# Pannel.net
KiCad netlist of a schematic drawn in EasyEDA Pro
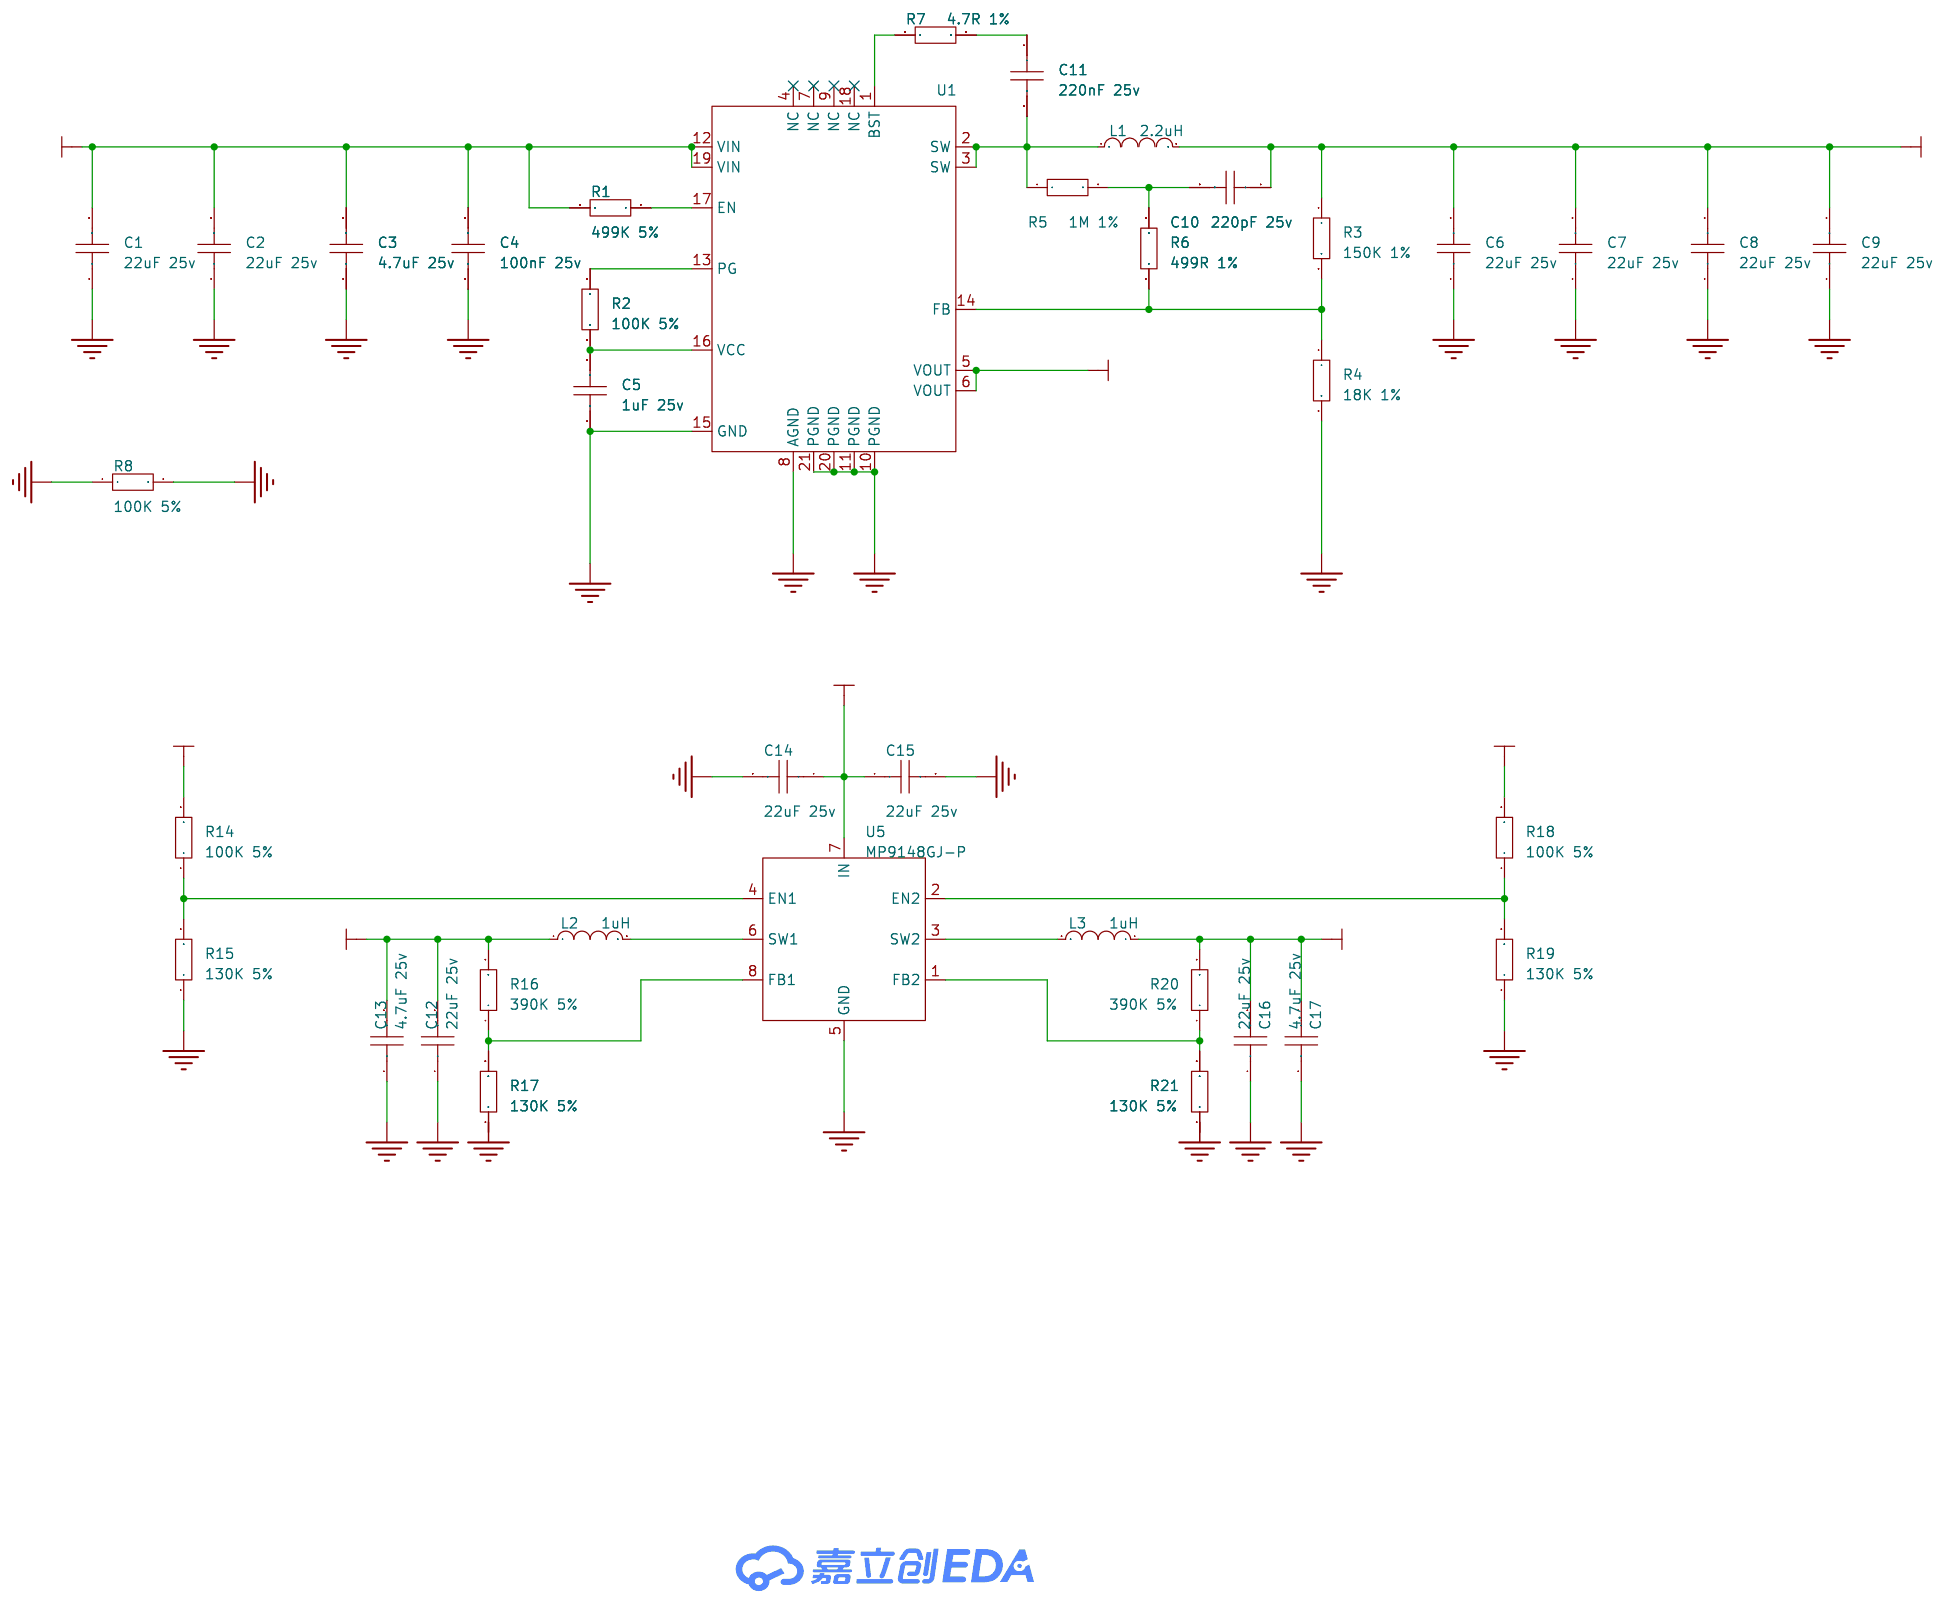
[diagram p0: PWR]
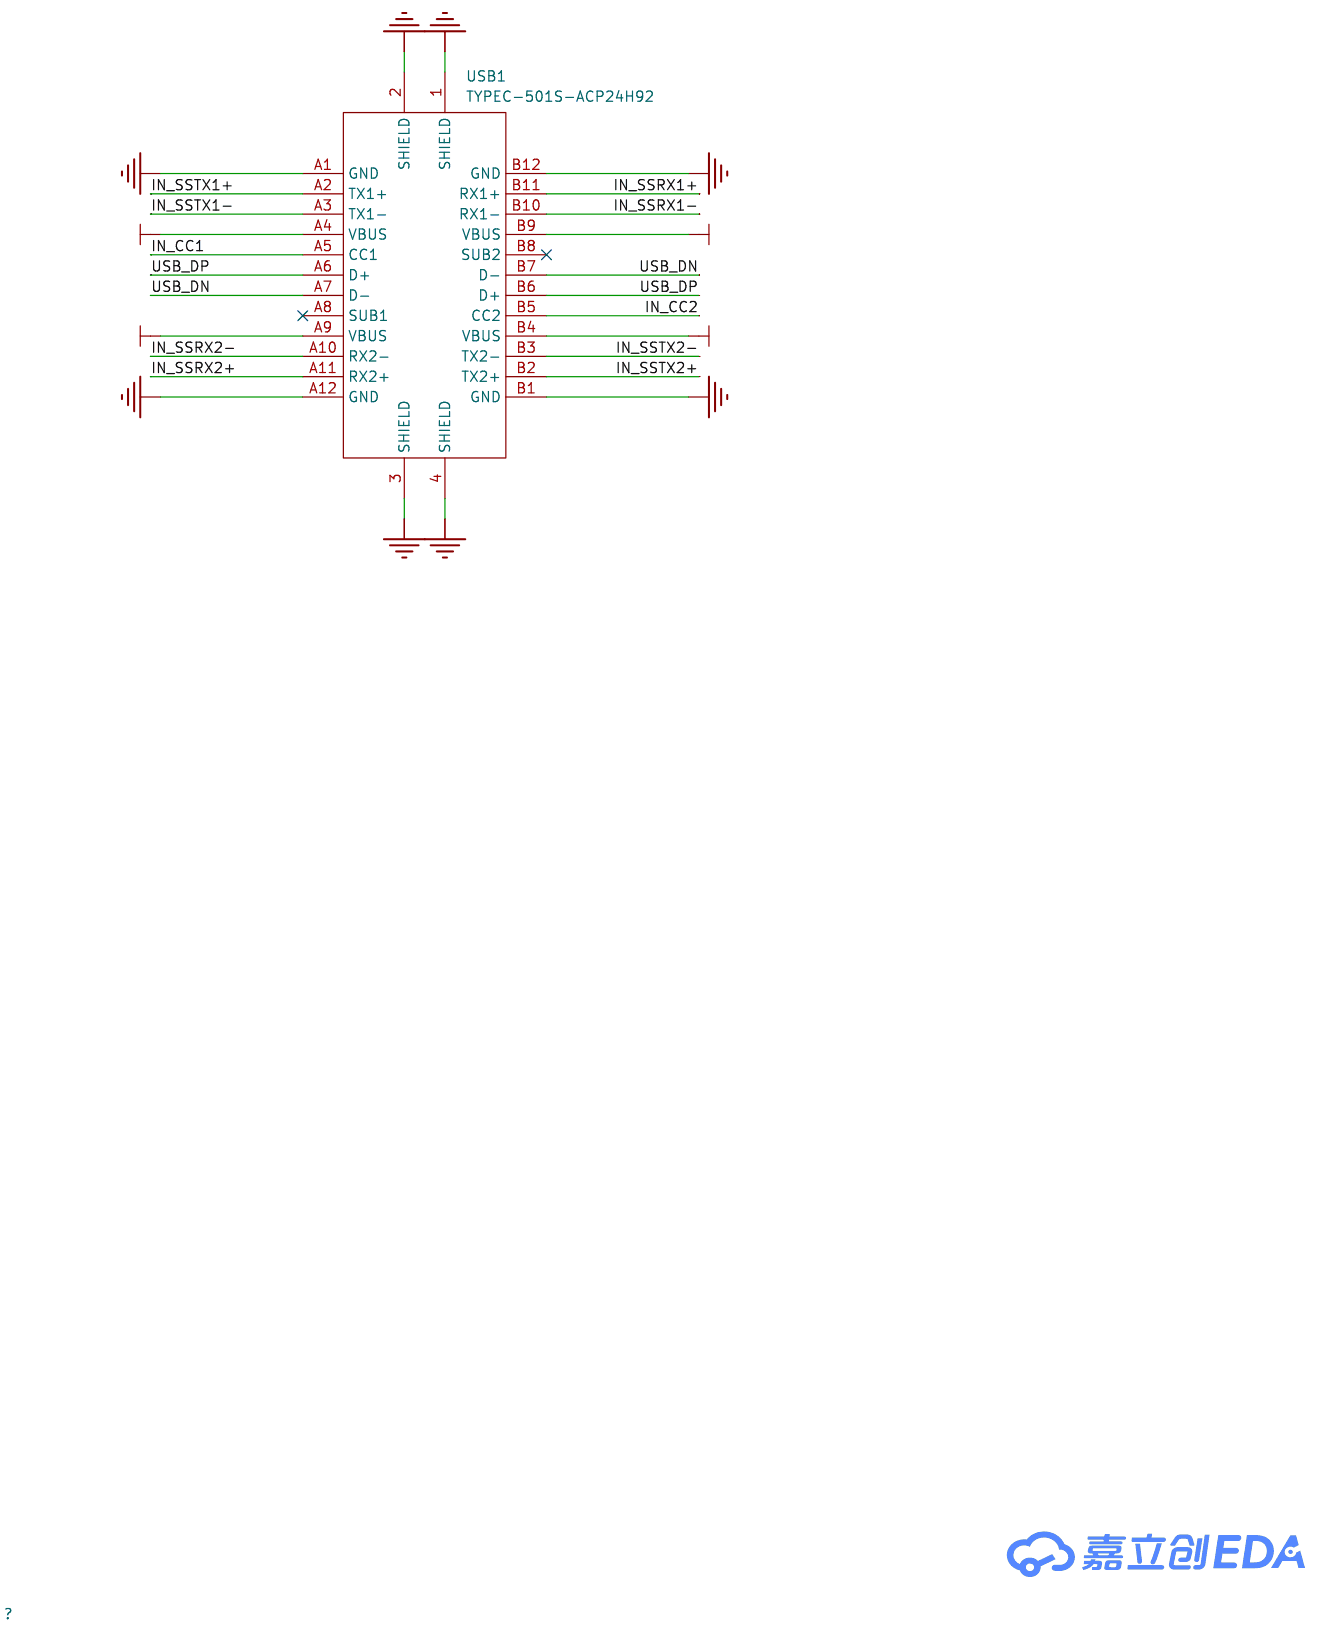
[diagram p1: Connector]
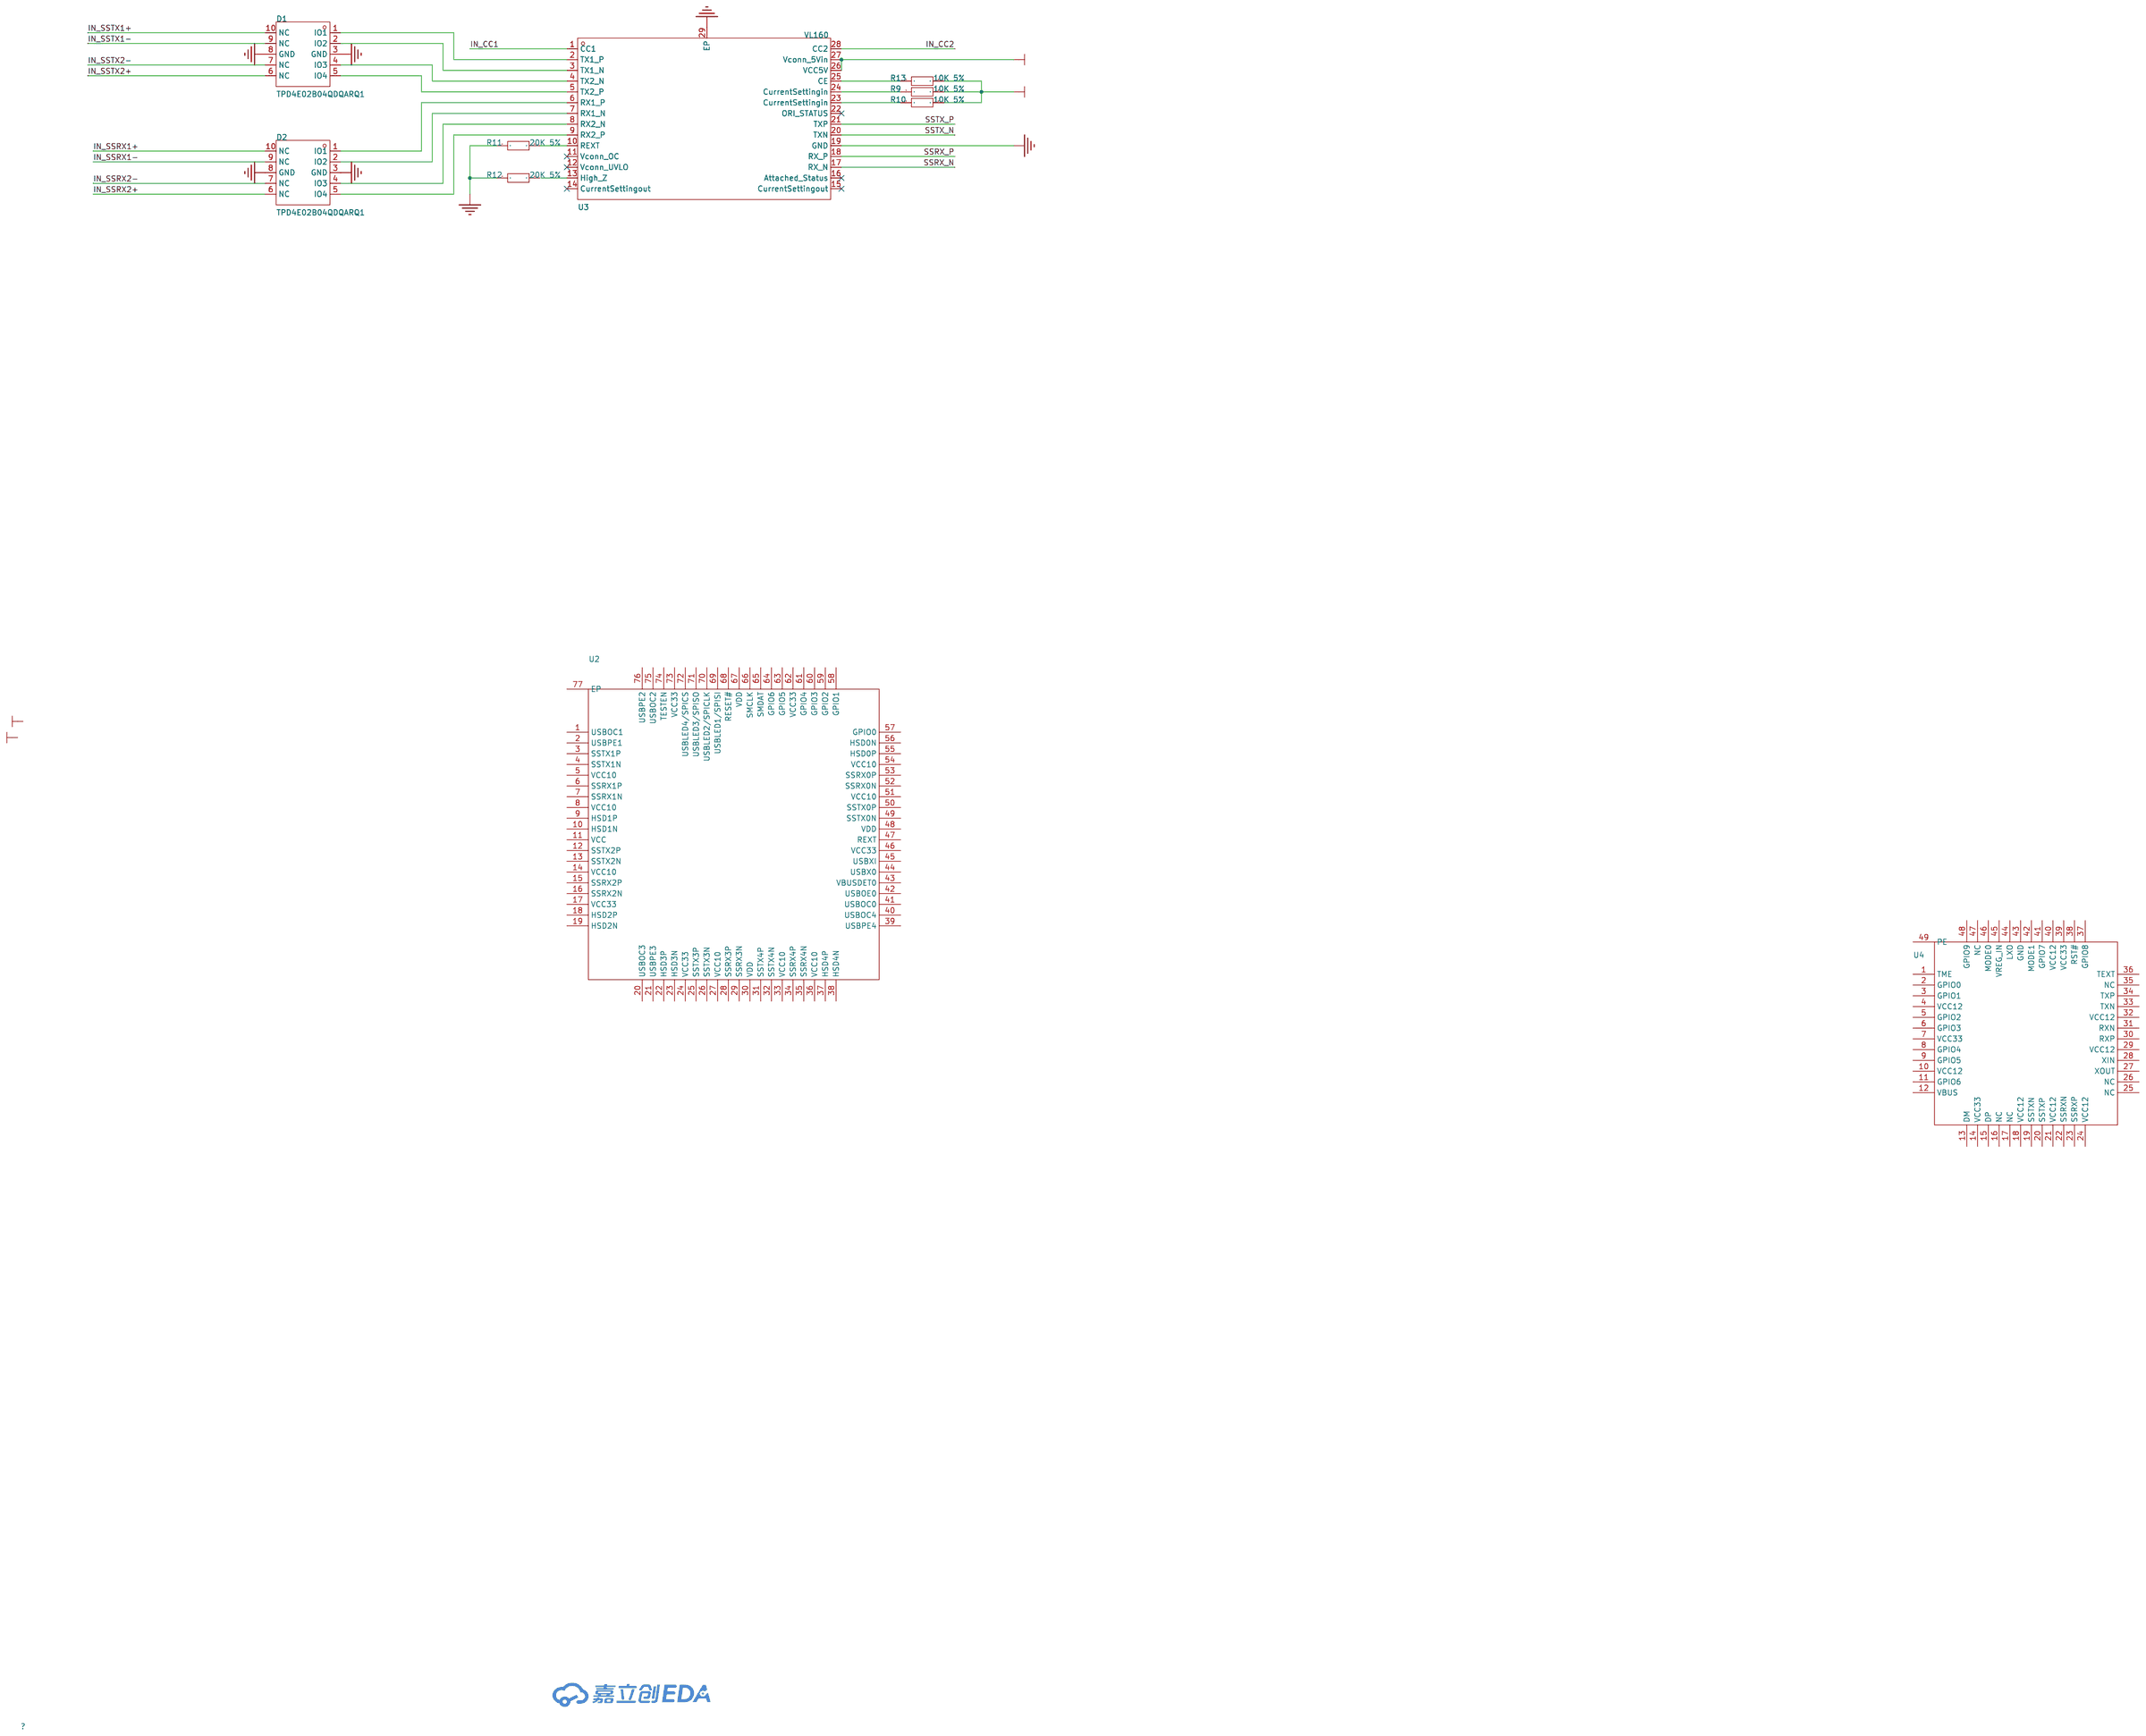
[diagram p2: Core]

(export (version "E")
  (design (tool "Eeschema 10.0.6"))
  (components
    (comp (ref "C1")
      (value "22uF 25v")
      (footprint "easyedapro:C0603")
      (libsource (lib "easyedapro") (part "Capacitance"))
    )
    (comp (ref "C2")
      (value "22uF 25v")
      (footprint "easyedapro:C0603")
      (libsource (lib "easyedapro") (part "Capacitance"))
    )
    (comp (ref "C3")
      (value "4.7uF 25v")
      (footprint "easyedapro:C0603")
      (libsource (lib "easyedapro") (part "Capacitance"))
    )
    (comp (ref "C4")
      (value "100nF 25v")
      (footprint "easyedapro:C0603")
      (libsource (lib "easyedapro") (part "Capacitance"))
    )
    (comp (ref "C5")
      (value "1uF 25v")
      (footprint "easyedapro:C0603")
      (libsource (lib "easyedapro") (part "Capacitance"))
    )
    (comp (ref "C6")
      (value "22uF 25v")
      (footprint "easyedapro:C0603")
      (libsource (lib "easyedapro") (part "Capacitance"))
    )
    (comp (ref "C7")
      (value "22uF 25v")
      (footprint "easyedapro:C0603")
      (libsource (lib "easyedapro") (part "Capacitance"))
    )
    (comp (ref "C8")
      (value "22uF 25v")
      (footprint "easyedapro:C0603")
      (libsource (lib "easyedapro") (part "Capacitance"))
    )
    (comp (ref "C9")
      (value "22uF 25v")
      (footprint "easyedapro:C0603")
      (libsource (lib "easyedapro") (part "Capacitance"))
    )
    (comp (ref "C10")
      (value "220pF 25v")
      (footprint "easyedapro:C0603")
      (libsource (lib "easyedapro") (part "Capacitance"))
    )
    (comp (ref "C11")
      (value "220nF 25v")
      (footprint "easyedapro:C0603")
      (libsource (lib "easyedapro") (part "Capacitance"))
    )
    (comp (ref "C12")
      (value "22uF 25v")
      (footprint "easyedapro:C0603")
      (libsource (lib "easyedapro") (part "Capacitance"))
    )
    (comp (ref "C13")
      (value "4.7uF 25v")
      (footprint "easyedapro:C0603")
      (libsource (lib "easyedapro") (part "Capacitance"))
    )
    (comp (ref "C14")
      (value "22uF 25v")
      (footprint "easyedapro:C0603")
      (libsource (lib "easyedapro") (part "Capacitance"))
    )
    (comp (ref "C15")
      (value "22uF 25v")
      (footprint "easyedapro:C0603")
      (libsource (lib "easyedapro") (part "Capacitance"))
    )
    (comp (ref "C16")
      (value "22uF 25v")
      (footprint "easyedapro:C0603")
      (libsource (lib "easyedapro") (part "Capacitance"))
    )
    (comp (ref "C17")
      (value "4.7uF 25v")
      (footprint "easyedapro:C0603")
      (libsource (lib "easyedapro") (part "Capacitance"))
    )
    (comp (ref "L1")
      (value "2.2uH")
      (footprint "easyedapro:L0603")
      (libsource (lib "easyedapro") (part "SDFL1608S100KTF"))
    )
    (comp (ref "L2")
      (value "1uH")
      (footprint "easyedapro:IND-SMD_L4.5-W4.1_YXMAA0402")
      (description "电感值:3.3uH;精度:±20%;额定电流:-;饱和电流(Isat):3.1A;直流电阻(DCR):65mΩ;")
      (fields (field (name "Manufacturer Part") "MDA4020-3R3M") (field (name "Manufacturer") "KOHERelec(科或)"))
      (libsource (lib "easyedapro") (part "MDA4020-3R3M"))
    )
    (comp (ref "L3")
      (value "1uH")
      (footprint "easyedapro:IND-SMD_L4.5-W4.1_YXMAA0402")
      (description "电感值:3.3uH;精度:±20%;额定电流:-;饱和电流(Isat):3.1A;直流电阻(DCR):65mΩ;")
      (fields (field (name "Manufacturer Part") "MDA4020-3R3M") (field (name "Manufacturer") "KOHERelec(科或)"))
      (libsource (lib "easyedapro") (part "MDA4020-3R3M"))
    )
    (comp (ref "R1")
      (value "499K 5%")
      (footprint "easyedapro:R0603")
      (libsource (lib "easyedapro") (part "电阻"))
    )
    (comp (ref "R2")
      (value "100K 5%")
      (footprint "easyedapro:R0603")
      (libsource (lib "easyedapro") (part "电阻"))
    )
    (comp (ref "R3")
      (value "150K 1%")
      (footprint "easyedapro:R0603")
      (libsource (lib "easyedapro") (part "电阻"))
    )
    (comp (ref "R4")
      (value "18K 1%")
      (footprint "easyedapro:R0603")
      (libsource (lib "easyedapro") (part "电阻"))
    )
    (comp (ref "R5")
      (value "1M 1%")
      (footprint "easyedapro:R0603")
      (libsource (lib "easyedapro") (part "电阻"))
    )
    (comp (ref "R6")
      (value "499R 1%")
      (footprint "easyedapro:R0603")
      (libsource (lib "easyedapro") (part "电阻"))
    )
    (comp (ref "R7")
      (value "4.7R 1%")
      (footprint "easyedapro:R0603")
      (libsource (lib "easyedapro") (part "电阻"))
    )
    (comp (ref "R8")
      (value "100K 5%")
      (footprint "easyedapro:R0603")
      (libsource (lib "easyedapro") (part "电阻"))
    )
    (comp (ref "R14")
      (value "100K 5%")
      (footprint "easyedapro:R0603")
      (libsource (lib "easyedapro") (part "电阻"))
    )
    (comp (ref "R15")
      (value "130K 5%")
      (footprint "easyedapro:R0603")
      (libsource (lib "easyedapro") (part "电阻"))
    )
    (comp (ref "R16")
      (value "390K 5%")
      (footprint "easyedapro:R0603")
      (libsource (lib "easyedapro") (part "电阻"))
    )
    (comp (ref "R17")
      (value "130K 5%")
      (footprint "easyedapro:R0603")
      (libsource (lib "easyedapro") (part "电阻"))
    )
    (comp (ref "R18")
      (value "100K 5%")
      (footprint "easyedapro:R0603")
      (libsource (lib "easyedapro") (part "电阻"))
    )
    (comp (ref "R19")
      (value "130K 5%")
      (footprint "easyedapro:R0603")
      (libsource (lib "easyedapro") (part "电阻"))
    )
    (comp (ref "R20")
      (value "390K 5%")
      (footprint "easyedapro:R0603")
      (libsource (lib "easyedapro") (part "电阻"))
    )
    (comp (ref "R21")
      (value "130K 5%")
      (footprint "easyedapro:R0603")
      (libsource (lib "easyedapro") (part "电阻"))
    )
    (comp (ref "U1") (value "~") (libsource (lib "easyedapro") (part "MP8757")))
    (comp (ref "U5")
      (value "MP9148GJ-P")
      (footprint "easyedapro:TSOT-23-8_L2.9-W1.6-P0.65-LS2.8-BR")
      (description "功能类型:降压型;输出类型:可调;工作电压:2.7V~6V;输出电压:608mV~5.5V;输出电流:1A;")
      (libsource (lib "easyedapro") (part "MP9148GJ-P"))
    )
    (comp (ref "USB1")
      (value "TYPEC-501S-ACP24H92")
      (footprint "easyedapro:USB-C-SMD_TYPEC-501S-ACP24H92")
      (fields (field (name "Manufacturer") "XUNPU(讯普)"))
      (libsource (lib "easyedapro") (part "TYPEC-501S-ACP24H92"))
    )
    (comp (ref "D1")
      (value "TPD4E02B04QDQARQ1")
      (footprint "easyedapro:USON-10_L2.5-W1.0-P0.50-BL")
      (fields (field (name "Manufacturer") "TI(德州仪器)"))
      (libsource (lib "easyedapro") (part "TPD4E02B04QDQARQ1"))
    )
    (comp (ref "D2")
      (value "TPD4E02B04QDQARQ1")
      (footprint "easyedapro:USON-10_L2.5-W1.0-P0.50-BL")
      (fields (field (name "Manufacturer") "TI(德州仪器)"))
      (libsource (lib "easyedapro") (part "TPD4E02B04QDQARQ1"))
    )
    (comp (ref "R9")
      (value "10K 5%")
      (footprint "easyedapro:R0603")
      (libsource (lib "easyedapro") (part "电阻"))
    )
    (comp (ref "R10")
      (value "10K 5%")
      (footprint "easyedapro:R0603")
      (libsource (lib "easyedapro") (part "电阻"))
    )
    (comp (ref "R11")
      (value "20K 5%")
      (footprint "easyedapro:R0603")
      (libsource (lib "easyedapro") (part "电阻"))
    )
    (comp (ref "R12")
      (value "20K 5%")
      (footprint "easyedapro:R0603")
      (libsource (lib "easyedapro") (part "电阻"))
    )
    (comp (ref "R13")
      (value "10K 5%")
      (footprint "easyedapro:R0603")
      (libsource (lib "easyedapro") (part "电阻"))
    )
    (comp (ref "U2")
      (value "~")
      (footprint "easyedapro:QFN-76_L9.0-W9.0-P0.40-TL-EP")
      (libsource (lib "easyedapro") (part "VL822"))
    )
    (comp (ref "U3")
      (value "VL160")
      (footprint "easyedapro:MQFN-28_L4.5-W3.5-P0.40-BL-EP")
      (description "应用功能:-;接口协议:-;")
      (libsource (lib "easyedapro") (part "VL160"))
    )
    (comp (ref "U4")
      (value "~")
      (footprint "easyedapro:QFN-48_L5.0-W5.0-P0.35-BL-EP3.7-1")
      (libsource (lib "easyedapro") (part "JMS578"))
    )
  )
  (nets
    (net (code "1") (name "GND") (class "Default")
      (node (ref "C1") (pin "1") (pinfunction "1_1") (pintype "input"))
      (node (ref "C12") (pin "1") (pinfunction "1_1") (pintype "input"))
      (node (ref "C13") (pin "1") (pinfunction "1_1") (pintype "input"))
      (node (ref "C14") (pin "2") (pinfunction "2_2") (pintype "input"))
      (node (ref "C15") (pin "2") (pinfunction "2_2") (pintype "input"))
      (node (ref "C16") (pin "1") (pinfunction "1_1") (pintype "input"))
      (node (ref "C17") (pin "1") (pinfunction "1_1") (pintype "input"))
      (node (ref "C2") (pin "1") (pinfunction "1_1") (pintype "input"))
      (node (ref "C3") (pin "1") (pinfunction "1_1") (pintype "input"))
      (node (ref "C4") (pin "1") (pinfunction "1_1") (pintype "input"))
      (node (ref "C5") (pin "1") (pinfunction "1_1") (pintype "input"))
      (node (ref "C6") (pin "1") (pinfunction "1_1") (pintype "input"))
      (node (ref "C7") (pin "1") (pinfunction "1_1") (pintype "input"))
      (node (ref "C8") (pin "1") (pinfunction "1_1") (pintype "input"))
      (node (ref "C9") (pin "1") (pinfunction "1_1") (pintype "input"))
      (node (ref "D1") (pin "3") (pinfunction "GND_3") (pintype "unspecified"))
      (node (ref "D1") (pin "8") (pinfunction "GND_8") (pintype "unspecified"))
      (node (ref "D2") (pin "3") (pinfunction "GND_3") (pintype "unspecified"))
      (node (ref "D2") (pin "8") (pinfunction "GND_8") (pintype "unspecified"))
      (node (ref "R11") (pin "1") (pinfunction "1_1") (pintype "input"))
      (node (ref "R12") (pin "1") (pinfunction "1_1") (pintype "input"))
      (node (ref "R15") (pin "1") (pinfunction "1_1") (pintype "input"))
      (node (ref "R17") (pin "1") (pinfunction "1_1") (pintype "input"))
      (node (ref "R19") (pin "1") (pinfunction "1_1") (pintype "input"))
      (node (ref "R21") (pin "1") (pinfunction "1_1") (pintype "input"))
      (node (ref "R4") (pin "2") (pinfunction "2_2") (pintype "input"))
      (node (ref "R8") (pin "1") (pinfunction "1_1") (pintype "input"))
      (node (ref "U1") (pin "15") (pinfunction "GND_15") (pintype "unspecified"))
      (node (ref "U1") (pin "8") (pinfunction "AGND_8") (pintype "unspecified"))
      (node (ref "U3") (pin "19") (pinfunction "GND_19") (pintype "unspecified"))
      (node (ref "U3") (pin "29") (pinfunction "EP_29") (pintype "unspecified"))
      (node (ref "U5") (pin "5") (pinfunction "GND_5") (pintype "unspecified"))
      (node (ref "USB1") (pin "1") (pinfunction "SHIELD_1") (pintype "unspecified"))
      (node (ref "USB1") (pin "2") (pinfunction "SHIELD_2") (pintype "unspecified"))
      (node (ref "USB1") (pin "3") (pinfunction "SHIELD_3") (pintype "unspecified"))
      (node (ref "USB1") (pin "4") (pinfunction "SHIELD_4") (pintype "unspecified"))
      (node (ref "USB1") (pin "A1") (pinfunction "GND_A1") (pintype "unspecified"))
      (node (ref "USB1") (pin "A12") (pinfunction "GND_A12") (pintype "unspecified"))
      (node (ref "USB1") (pin "B1") (pinfunction "GND_B1") (pintype "unspecified"))
      (node (ref "USB1") (pin "B12") (pinfunction "GND_B12") (pintype "unspecified"))
    )
    (net (code "2") (name "IN_CC1") (class "Default")
      (node (ref "U3") (pin "1") (pinfunction "CC1_1") (pintype "unspecified"))
      (node (ref "USB1") (pin "A5") (pinfunction "CC1_A5") (pintype "unspecified"))
    )
    (net (code "3") (name "IN_CC2") (class "Default")
      (node (ref "U3") (pin "28") (pinfunction "CC2_28") (pintype "unspecified"))
      (node (ref "USB1") (pin "B5") (pinfunction "CC2_B5") (pintype "unspecified"))
    )
    (net (code "4") (name "IN_SSRX1+") (class "Default")
      (node (ref "D2") (pin "10") (pinfunction "NC_10") (pintype "unspecified"))
      (node (ref "USB1") (pin "B11") (pinfunction "RX1+_B11") (pintype "unspecified"))
    )
    (net (code "5") (name "IN_SSRX1-") (class "Default")
      (node (ref "D2") (pin "9") (pinfunction "NC_9") (pintype "unspecified"))
      (node (ref "USB1") (pin "B10") (pinfunction "RX1-_B10") (pintype "unspecified"))
    )
    (net (code "6") (name "IN_SSRX2+") (class "Default")
      (node (ref "D2") (pin "6") (pinfunction "NC_6") (pintype "unspecified"))
      (node (ref "USB1") (pin "A11") (pinfunction "RX2+_A11") (pintype "unspecified"))
    )
    (net (code "7") (name "IN_SSRX2-") (class "Default")
      (node (ref "D2") (pin "7") (pinfunction "NC_7") (pintype "unspecified"))
      (node (ref "USB1") (pin "A10") (pinfunction "RX2-_A10") (pintype "unspecified"))
    )
    (net (code "8") (name "IN_SSTX1+") (class "Default")
      (node (ref "D1") (pin "10") (pinfunction "NC_10") (pintype "unspecified"))
      (node (ref "USB1") (pin "A2") (pinfunction "TX1+_A2") (pintype "unspecified"))
    )
    (net (code "9") (name "IN_SSTX1-") (class "Default")
      (node (ref "D1") (pin "9") (pinfunction "NC_9") (pintype "unspecified"))
      (node (ref "USB1") (pin "A3") (pinfunction "TX1-_A3") (pintype "unspecified"))
    )
    (net (code "10") (name "IN_SSTX2+") (class "Default")
      (node (ref "D1") (pin "6") (pinfunction "NC_6") (pintype "unspecified"))
      (node (ref "USB1") (pin "B2") (pinfunction "TX2+_B2") (pintype "unspecified"))
    )
    (net (code "11") (name "IN_SSTX2-") (class "Default")
      (node (ref "D1") (pin "7") (pinfunction "NC_7") (pintype "unspecified"))
      (node (ref "USB1") (pin "B3") (pinfunction "TX2-_B3") (pintype "unspecified"))
    )
    (net (code "12") (name "Net-(C10-Pad2)") (class "Default")
      (node (ref "C10") (pin "2") (pinfunction "2_2") (pintype "input"))
      (node (ref "R5") (pin "2") (pinfunction "2_2") (pintype "input"))
      (node (ref "R6") (pin "2") (pinfunction "2_2") (pintype "input"))
    )
    (net (code "13") (name "Net-(C11-Pad1)") (class "Default")
      (node (ref "C11") (pin "1") (pinfunction "1_1") (pintype "input"))
      (node (ref "R7") (pin "2") (pinfunction "2_2") (pintype "input"))
    )
    (net (code "14") (name "Net-(C11-Pad2)") (class "Default")
      (node (ref "C11") (pin "2") (pinfunction "2_2") (pintype "input"))
      (node (ref "L1") (pin "1") (pinfunction "1_1") (pintype "unspecified"))
      (node (ref "R5") (pin "1") (pinfunction "1_1") (pintype "input"))
      (node (ref "U1") (pin "2") (pinfunction "SW_2") (pintype "unspecified"))
      (node (ref "U1") (pin "3") (pinfunction "SW_3") (pintype "unspecified"))
    )
    (net (code "15") (name "Net-(D1-IO1)") (class "Default")
      (node (ref "D1") (pin "1") (pinfunction "IO1_1") (pintype "unspecified"))
      (node (ref "U3") (pin "2") (pinfunction "TX1_P_2") (pintype "unspecified"))
    )
    (net (code "16") (name "Net-(D1-IO2)") (class "Default")
      (node (ref "D1") (pin "2") (pinfunction "IO2_2") (pintype "unspecified"))
      (node (ref "U3") (pin "3") (pinfunction "TX1_N_3") (pintype "unspecified"))
    )
    (net (code "17") (name "Net-(D1-IO3)") (class "Default")
      (node (ref "D1") (pin "4") (pinfunction "IO3_4") (pintype "unspecified"))
      (node (ref "U3") (pin "4") (pinfunction "TX2_N_4") (pintype "unspecified"))
    )
    (net (code "18") (name "Net-(D1-IO4)") (class "Default")
      (node (ref "D1") (pin "5") (pinfunction "IO4_5") (pintype "unspecified"))
      (node (ref "U3") (pin "5") (pinfunction "TX2_P_5") (pintype "unspecified"))
    )
    (net (code "19") (name "Net-(D2-IO1)") (class "Default")
      (node (ref "D2") (pin "1") (pinfunction "IO1_1") (pintype "unspecified"))
      (node (ref "U3") (pin "6") (pinfunction "RX1_P_6") (pintype "unspecified"))
    )
    (net (code "20") (name "Net-(D2-IO2)") (class "Default")
      (node (ref "D2") (pin "2") (pinfunction "IO2_2") (pintype "unspecified"))
      (node (ref "U3") (pin "7") (pinfunction "RX1_N_7") (pintype "unspecified"))
    )
    (net (code "21") (name "Net-(D2-IO3)") (class "Default")
      (node (ref "D2") (pin "4") (pinfunction "IO3_4") (pintype "unspecified"))
      (node (ref "U3") (pin "8") (pinfunction "RX2_N_8") (pintype "unspecified"))
    )
    (net (code "22") (name "Net-(D2-IO4)") (class "Default")
      (node (ref "D2") (pin "5") (pinfunction "IO4_5") (pintype "unspecified"))
      (node (ref "U3") (pin "9") (pinfunction "RX2_P_9") (pintype "unspecified"))
    )
    (net (code "23") (name "Net-(R9-Pad1)") (class "Default")
      (node (ref "R9") (pin "1") (pinfunction "1_1") (pintype "input"))
      (node (ref "U3") (pin "24") (pinfunction "CurrentSettingin_24") (pintype "unspecified"))
    )
    (net (code "24") (name "Net-(R10-Pad1)") (class "Default")
      (node (ref "R10") (pin "1") (pinfunction "1_1") (pintype "input"))
      (node (ref "U3") (pin "23") (pinfunction "CurrentSettingin_23") (pintype "unspecified"))
    )
    (net (code "25") (name "Net-(U1-BST)") (class "Default")
      (node (ref "R7") (pin "1") (pinfunction "1_1") (pintype "input"))
      (node (ref "U1") (pin "1") (pinfunction "BST_1") (pintype "unspecified"))
    )
    (net (code "26") (name "Net-(U1-EN)") (class "Default")
      (node (ref "R1") (pin "1") (pinfunction "1_1") (pintype "input"))
      (node (ref "U1") (pin "17") (pinfunction "EN_17") (pintype "unspecified"))
    )
    (net (code "27") (name "Net-(U1-FB)") (class "Default")
      (node (ref "R3") (pin "2") (pinfunction "2_2") (pintype "input"))
      (node (ref "R4") (pin "1") (pinfunction "1_1") (pintype "input"))
      (node (ref "R6") (pin "1") (pinfunction "1_1") (pintype "input"))
      (node (ref "U1") (pin "14") (pinfunction "FB_14") (pintype "unspecified"))
    )
    (net (code "28") (name "Net-(U1-PG)") (class "Default")
      (node (ref "R2") (pin "1") (pinfunction "1_1") (pintype "input"))
      (node (ref "U1") (pin "13") (pinfunction "PG_13") (pintype "unspecified"))
    )
    (net (code "29") (name "Net-(U1-VCC)") (class "Default")
      (node (ref "C5") (pin "2") (pinfunction "2_2") (pintype "input"))
      (node (ref "R2") (pin "2") (pinfunction "2_2") (pintype "input"))
      (node (ref "U1") (pin "16") (pinfunction "VCC_16") (pintype "unspecified"))
    )
    (net (code "30") (name "Net-(U3-CE)") (class "Default")
      (node (ref "R13") (pin "1") (pinfunction "1_1") (pintype "input"))
      (node (ref "U3") (pin "25") (pinfunction "CE_25") (pintype "unspecified"))
    )
    (net (code "31") (name "Net-(U3-REXT)") (class "Default")
      (node (ref "R11") (pin "2") (pinfunction "2_2") (pintype "input"))
      (node (ref "U3") (pin "10") (pinfunction "REXT_10") (pintype "unspecified"))
    )
    (net (code "32") (name "Net-(U5-EN1)") (class "Default")
      (node (ref "R14") (pin "1") (pinfunction "1_1") (pintype "input"))
      (node (ref "R15") (pin "2") (pinfunction "2_2") (pintype "input"))
      (node (ref "U5") (pin "4") (pinfunction "EN1_4") (pintype "unspecified"))
    )
    (net (code "33") (name "Net-(U5-EN2)") (class "Default")
      (node (ref "R18") (pin "1") (pinfunction "1_1") (pintype "input"))
      (node (ref "R19") (pin "2") (pinfunction "2_2") (pintype "input"))
      (node (ref "U5") (pin "2") (pinfunction "EN2_2") (pintype "unspecified"))
    )
    (net (code "34") (name "Net-(U5-FB1)") (class "Default")
      (node (ref "R16") (pin "1") (pinfunction "1_1") (pintype "input"))
      (node (ref "R17") (pin "2") (pinfunction "2_2") (pintype "input"))
      (node (ref "U5") (pin "8") (pinfunction "FB1_8") (pintype "unspecified"))
    )
    (net (code "35") (name "Net-(U5-FB2)") (class "Default")
      (node (ref "R20") (pin "1") (pinfunction "1_1") (pintype "input"))
      (node (ref "R21") (pin "2") (pinfunction "2_2") (pintype "input"))
      (node (ref "U5") (pin "1") (pinfunction "FB2_1") (pintype "unspecified"))
    )
    (net (code "36") (name "Net-(U5-SW1)") (class "Default")
      (node (ref "L2") (pin "2") (pinfunction "2_2") (pintype "unspecified"))
      (node (ref "U5") (pin "6") (pinfunction "SW1_6") (pintype "unspecified"))
    )
    (net (code "37") (name "Net-(U5-SW2)") (class "Default")
      (node (ref "L3") (pin "2") (pinfunction "2_2") (pintype "unspecified"))
      (node (ref "U5") (pin "3") (pinfunction "SW2_3") (pintype "unspecified"))
    )
    (net (code "38") (name "PGND") (class "Default")
      (node (ref "R8") (pin "2") (pinfunction "2_2") (pintype "input"))
      (node (ref "U1") (pin "10") (pinfunction "PGND_10") (pintype "unspecified"))
      (node (ref "U1") (pin "11") (pinfunction "PGND_11") (pintype "unspecified"))
      (node (ref "U1") (pin "20") (pinfunction "PGND_20") (pintype "unspecified"))
      (node (ref "U1") (pin "21") (pinfunction "PGND_21") (pintype "unspecified"))
    )
    (net (code "39") (name "SSRX_N") (class "Default")
      (node (ref "U3") (pin "17") (pinfunction "RX_N_17") (pintype "unspecified"))
    )
    (net (code "40") (name "SSRX_P") (class "Default")
      (node (ref "U3") (pin "18") (pinfunction "RX_P_18") (pintype "unspecified"))
    )
    (net (code "41") (name "SSTX_N") (class "Default")
      (node (ref "U3") (pin "20") (pinfunction "TXN_20") (pintype "unspecified"))
    )
    (net (code "42") (name "SSTX_P") (class "Default")
      (node (ref "U3") (pin "21") (pinfunction "TXP_21") (pintype "unspecified"))
    )
    (net (code "43") (name "USB_DN") (class "Default")
      (node (ref "USB1") (pin "A7") (pinfunction "D-_A7") (pintype "unspecified"))
      (node (ref "USB1") (pin "B7") (pinfunction "D-_B7") (pintype "unspecified"))
    )
    (net (code "44") (name "USB_DP") (class "Default")
      (node (ref "USB1") (pin "A6") (pinfunction "D+_A6") (pintype "unspecified"))
      (node (ref "USB1") (pin "B6") (pinfunction "D+_B6") (pintype "unspecified"))
    )
    (net (code "45") (name "VBUS") (class "Default")
      (node (ref "C14") (pin "1") (pinfunction "1_1") (pintype "input"))
      (node (ref "C15") (pin "1") (pinfunction "1_1") (pintype "input"))
      (node (ref "R10") (pin "2") (pinfunction "2_2") (pintype "input"))
      (node (ref "R13") (pin "2") (pinfunction "2_2") (pintype "input"))
      (node (ref "R14") (pin "2") (pinfunction "2_2") (pintype "input"))
      (node (ref "R18") (pin "2") (pinfunction "2_2") (pintype "input"))
      (node (ref "R9") (pin "2") (pinfunction "2_2") (pintype "input"))
      (node (ref "U3") (pin "26") (pinfunction "VCC5V_26") (pintype "unspecified"))
      (node (ref "U3") (pin "27") (pinfunction "Vconn_5Vin_27") (pintype "unspecified"))
      (node (ref "U5") (pin "7") (pinfunction "IN_7") (pintype "unspecified"))
      (node (ref "USB1") (pin "A4") (pinfunction "VBUS_A4") (pintype "unspecified"))
      (node (ref "USB1") (pin "A9") (pinfunction "VBUS_A9") (pintype "unspecified"))
      (node (ref "USB1") (pin "B4") (pinfunction "VBUS_B4") (pintype "unspecified"))
      (node (ref "USB1") (pin "B9") (pinfunction "VBUS_B9") (pintype "unspecified"))
    )
    (net (code "46") (name "VCC1V0") (class "Default")
      (node (ref "C12") (pin "2") (pinfunction "2_2") (pintype "input"))
      (node (ref "C13") (pin "2") (pinfunction "2_2") (pintype "input"))
      (node (ref "L2") (pin "1") (pinfunction "1_1") (pintype "unspecified"))
      (node (ref "R16") (pin "2") (pinfunction "2_2") (pintype "input"))
    )
    (net (code "47") (name "VCC3V3") (class "Default")
      (node (ref "C16") (pin "2") (pinfunction "2_2") (pintype "input"))
      (node (ref "C17") (pin "2") (pinfunction "2_2") (pintype "input"))
      (node (ref "L3") (pin "1") (pinfunction "1_1") (pintype "unspecified"))
      (node (ref "R20") (pin "2") (pinfunction "2_2") (pintype "input"))
    )
    (net (code "48") (name "VCC5V") (class "Default")
      (node (ref "C10") (pin "1") (pinfunction "1_1") (pintype "input"))
      (node (ref "C6") (pin "2") (pinfunction "2_2") (pintype "input"))
      (node (ref "C7") (pin "2") (pinfunction "2_2") (pintype "input"))
      (node (ref "C8") (pin "2") (pinfunction "2_2") (pintype "input"))
      (node (ref "C9") (pin "2") (pinfunction "2_2") (pintype "input"))
      (node (ref "L1") (pin "2") (pinfunction "2_2") (pintype "unspecified"))
      (node (ref "R3") (pin "1") (pinfunction "1_1") (pintype "input"))
      (node (ref "U1") (pin "5") (pinfunction "VOUT_5") (pintype "unspecified"))
      (node (ref "U1") (pin "6") (pinfunction "VOUT_6") (pintype "unspecified"))
    )
    (net (code "49") (name "VCC12V") (class "Default")
      (node (ref "C1") (pin "2") (pinfunction "2_2") (pintype "input"))
      (node (ref "C2") (pin "2") (pinfunction "2_2") (pintype "input"))
      (node (ref "C3") (pin "2") (pinfunction "2_2") (pintype "input"))
      (node (ref "C4") (pin "2") (pinfunction "2_2") (pintype "input"))
      (node (ref "R1") (pin "2") (pinfunction "2_2") (pintype "input"))
      (node (ref "U1") (pin "12") (pinfunction "VIN_12") (pintype "unspecified"))
      (node (ref "U1") (pin "19") (pinfunction "VIN_19") (pintype "unspecified"))
    )
    (net (code "50") (name "unconnected-(R12-Pad2)") (class "Default")
      (node (ref "R12") (pin "2") (pinfunction "2_2") (pintype "input"))
    )
    (net (code "51") (name "unconnected-(U1-NC-Pad4)") (class "Default")
      (node (ref "U1") (pin "4") (pinfunction "NC_4") (pintype "unspecified+no_connect"))
    )
    (net (code "52") (name "unconnected-(U1-NC-Pad7)") (class "Default")
      (node (ref "U1") (pin "7") (pinfunction "NC_7") (pintype "unspecified+no_connect"))
    )
    (net (code "53") (name "unconnected-(U1-NC-Pad9)") (class "Default")
      (node (ref "U1") (pin "9") (pinfunction "NC_9") (pintype "unspecified+no_connect"))
    )
    (net (code "54") (name "unconnected-(U1-NC-Pad18)") (class "Default")
      (node (ref "U1") (pin "18") (pinfunction "NC_18") (pintype "unspecified+no_connect"))
    )
    (net (code "55") (name "unconnected-(U2-EP-Pad77)") (class "Default")
      (node (ref "U2") (pin "77") (pinfunction "EP_77") (pintype "input"))
    )
    (net (code "56") (name "unconnected-(U2-GPIO0-Pad57)") (class "Default")
      (node (ref "U2") (pin "57") (pinfunction "GPIO0_57") (pintype "input"))
    )
    (net (code "57") (name "unconnected-(U2-GPIO1-Pad58)") (class "Default")
      (node (ref "U2") (pin "58") (pinfunction "GPIO1_58") (pintype "input"))
    )
    (net (code "58") (name "unconnected-(U2-GPIO2-Pad59)") (class "Default")
      (node (ref "U2") (pin "59") (pinfunction "GPIO2_59") (pintype "input"))
    )
    (net (code "59") (name "unconnected-(U2-GPIO3-Pad60)") (class "Default")
      (node (ref "U2") (pin "60") (pinfunction "GPIO3_60") (pintype "input"))
    )
    (net (code "60") (name "unconnected-(U2-GPIO4-Pad61)") (class "Default")
      (node (ref "U2") (pin "61") (pinfunction "GPIO4_61") (pintype "input"))
    )
    (net (code "61") (name "unconnected-(U2-GPIO5-Pad63)") (class "Default")
      (node (ref "U2") (pin "63") (pinfunction "GPIO5_63") (pintype "input"))
    )
    (net (code "62") (name "unconnected-(U2-GPIO6-Pad64)") (class "Default")
      (node (ref "U2") (pin "64") (pinfunction "GPIO6_64") (pintype "input"))
    )
    (net (code "63") (name "unconnected-(U2-HSD0N-Pad56)") (class "Default")
      (node (ref "U2") (pin "56") (pinfunction "HSD0N_56") (pintype "input"))
    )
    (net (code "64") (name "unconnected-(U2-HSD0P-Pad55)") (class "Default")
      (node (ref "U2") (pin "55") (pinfunction "HSD0P_55") (pintype "input"))
    )
    (net (code "65") (name "unconnected-(U2-HSD1N-Pad10)") (class "Default")
      (node (ref "U2") (pin "10") (pinfunction "HSD1N_10") (pintype "input"))
    )
    (net (code "66") (name "unconnected-(U2-HSD1P-Pad9)") (class "Default")
      (node (ref "U2") (pin "9") (pinfunction "HSD1P_9") (pintype "input"))
    )
    (net (code "67") (name "unconnected-(U2-HSD2N-Pad19)") (class "Default")
      (node (ref "U2") (pin "19") (pinfunction "HSD2N_19") (pintype "input"))
    )
    (net (code "68") (name "unconnected-(U2-HSD2P-Pad18)") (class "Default")
      (node (ref "U2") (pin "18") (pinfunction "HSD2P_18") (pintype "input"))
    )
    (net (code "69") (name "unconnected-(U2-HSD3N-Pad23)") (class "Default")
      (node (ref "U2") (pin "23") (pinfunction "HSD3N_23") (pintype "input"))
    )
    (net (code "70") (name "unconnected-(U2-HSD3P-Pad22)") (class "Default")
      (node (ref "U2") (pin "22") (pinfunction "HSD3P_22") (pintype "input"))
    )
    (net (code "71") (name "unconnected-(U2-HSD4N-Pad38)") (class "Default")
      (node (ref "U2") (pin "38") (pinfunction "HSD4N_38") (pintype "input"))
    )
    (net (code "72") (name "unconnected-(U2-HSD4P-Pad37)") (class "Default")
      (node (ref "U2") (pin "37") (pinfunction "HSD4P_37") (pintype "input"))
    )
    (net (code "73") (name "unconnected-(U2-RESET#-Pad68)") (class "Default")
      (node (ref "U2") (pin "68") (pinfunction "RESET#_68") (pintype "input"))
    )
    (net (code "74") (name "unconnected-(U2-REXT-Pad47)") (class "Default")
      (node (ref "U2") (pin "47") (pinfunction "REXT_47") (pintype "input"))
    )
    (net (code "75") (name "unconnected-(U2-SMCLK-Pad66)") (class "Default")
      (node (ref "U2") (pin "66") (pinfunction "SMCLK_66") (pintype "input"))
    )
    (net (code "76") (name "unconnected-(U2-SMDAT-Pad65)") (class "Default")
      (node (ref "U2") (pin "65") (pinfunction "SMDAT_65") (pintype "input"))
    )
    (net (code "77") (name "unconnected-(U2-SSRX0N-Pad52)") (class "Default")
      (node (ref "U2") (pin "52") (pinfunction "SSRX0N_52") (pintype "input"))
    )
    (net (code "78") (name "unconnected-(U2-SSRX0P-Pad53)") (class "Default")
      (node (ref "U2") (pin "53") (pinfunction "SSRX0P_53") (pintype "input"))
    )
    (net (code "79") (name "unconnected-(U2-SSRX1N-Pad7)") (class "Default")
      (node (ref "U2") (pin "7") (pinfunction "SSRX1N_7") (pintype "input"))
    )
    (net (code "80") (name "unconnected-(U2-SSRX1P-Pad6)") (class "Default")
      (node (ref "U2") (pin "6") (pinfunction "SSRX1P_6") (pintype "input"))
    )
    (net (code "81") (name "unconnected-(U2-SSRX2N-Pad16)") (class "Default")
      (node (ref "U2") (pin "16") (pinfunction "SSRX2N_16") (pintype "input"))
    )
    (net (code "82") (name "unconnected-(U2-SSRX2P-Pad15)") (class "Default")
      (node (ref "U2") (pin "15") (pinfunction "SSRX2P_15") (pintype "input"))
    )
    (net (code "83") (name "unconnected-(U2-SSRX3N-Pad29)") (class "Default")
      (node (ref "U2") (pin "29") (pinfunction "SSRX3N_29") (pintype "input"))
    )
    (net (code "84") (name "unconnected-(U2-SSRX3P-Pad28)") (class "Default")
      (node (ref "U2") (pin "28") (pinfunction "SSRX3P_28") (pintype "input"))
    )
    (net (code "85") (name "unconnected-(U2-SSRX4N-Pad35)") (class "Default")
      (node (ref "U2") (pin "35") (pinfunction "SSRX4N_35") (pintype "input"))
    )
    (net (code "86") (name "unconnected-(U2-SSRX4P-Pad34)") (class "Default")
      (node (ref "U2") (pin "34") (pinfunction "SSRX4P_34") (pintype "input"))
    )
    (net (code "87") (name "unconnected-(U2-SSTX0N-Pad49)") (class "Default")
      (node (ref "U2") (pin "49") (pinfunction "SSTX0N_49") (pintype "input"))
    )
    (net (code "88") (name "unconnected-(U2-SSTX0P-Pad50)") (class "Default")
      (node (ref "U2") (pin "50") (pinfunction "SSTX0P_50") (pintype "input"))
    )
    (net (code "89") (name "unconnected-(U2-SSTX1N-Pad4)") (class "Default")
      (node (ref "U2") (pin "4") (pinfunction "SSTX1N_4") (pintype "input"))
    )
    (net (code "90") (name "unconnected-(U2-SSTX1P-Pad3)") (class "Default")
      (node (ref "U2") (pin "3") (pinfunction "SSTX1P_3") (pintype "input"))
    )
    (net (code "91") (name "unconnected-(U2-SSTX2N-Pad13)") (class "Default")
      (node (ref "U2") (pin "13") (pinfunction "SSTX2N_13") (pintype "input"))
    )
    (net (code "92") (name "unconnected-(U2-SSTX2P-Pad12)") (class "Default")
      (node (ref "U2") (pin "12") (pinfunction "SSTX2P_12") (pintype "input"))
    )
    (net (code "93") (name "unconnected-(U2-SSTX3N-Pad26)") (class "Default")
      (node (ref "U2") (pin "26") (pinfunction "SSTX3N_26") (pintype "input"))
    )
    (net (code "94") (name "unconnected-(U2-SSTX3P-Pad25)") (class "Default")
      (node (ref "U2") (pin "25") (pinfunction "SSTX3P_25") (pintype "input"))
    )
    (net (code "95") (name "unconnected-(U2-SSTX4N-Pad32)") (class "Default")
      (node (ref "U2") (pin "32") (pinfunction "SSTX4N_32") (pintype "input"))
    )
    (net (code "96") (name "unconnected-(U2-SSTX4P-Pad31)") (class "Default")
      (node (ref "U2") (pin "31") (pinfunction "SSTX4P_31") (pintype "input"))
    )
    (net (code "97") (name "unconnected-(U2-TESTEN-Pad74)") (class "Default")
      (node (ref "U2") (pin "74") (pinfunction "TESTEN_74") (pintype "input"))
    )
    (net (code "98") (name "unconnected-(U2-USBLED1{slash}SPISI-Pad69)") (class "Default")
      (node (ref "U2") (pin "69") (pinfunction "USBLED1/SPISI_69") (pintype "input"))
    )
    (net (code "99") (name "unconnected-(U2-USBLED2{slash}SPICLK-Pad70)") (class "Default")
      (node (ref "U2") (pin "70") (pinfunction "USBLED2/SPICLK_70") (pintype "input"))
    )
    (net (code "100") (name "unconnected-(U2-USBLED3{slash}SPISO-Pad71)") (class "Default")
      (node (ref "U2") (pin "71") (pinfunction "USBLED3/SPISO_71") (pintype "input"))
    )
    (net (code "101") (name "unconnected-(U2-USBLED4{slash}SPICS-Pad72)") (class "Default")
      (node (ref "U2") (pin "72") (pinfunction "USBLED4/SPICS_72") (pintype "input"))
    )
    (net (code "102") (name "unconnected-(U2-USBOC0-Pad41)") (class "Default")
      (node (ref "U2") (pin "41") (pinfunction "USBOC0_41") (pintype "input"))
    )
    (net (code "103") (name "unconnected-(U2-USBOC1-Pad1)") (class "Default")
      (node (ref "U2") (pin "1") (pinfunction "USBOC1_1") (pintype "input"))
    )
    (net (code "104") (name "unconnected-(U2-USBOC2-Pad75)") (class "Default")
      (node (ref "U2") (pin "75") (pinfunction "USBOC2_75") (pintype "input"))
    )
    (net (code "105") (name "unconnected-(U2-USBOC3-Pad20)") (class "Default")
      (node (ref "U2") (pin "20") (pinfunction "USBOC3_20") (pintype "input"))
    )
    (net (code "106") (name "unconnected-(U2-USBOC4-Pad40)") (class "Default")
      (node (ref "U2") (pin "40") (pinfunction "USBOC4_40") (pintype "input"))
    )
    (net (code "107") (name "unconnected-(U2-USBOE0-Pad42)") (class "Default")
      (node (ref "U2") (pin "42") (pinfunction "USBOE0_42") (pintype "input"))
    )
    (net (code "108") (name "unconnected-(U2-USBPE1-Pad2)") (class "Default")
      (node (ref "U2") (pin "2") (pinfunction "USBPE1_2") (pintype "input"))
    )
    (net (code "109") (name "unconnected-(U2-USBPE2-Pad76)") (class "Default")
      (node (ref "U2") (pin "76") (pinfunction "USBPE2_76") (pintype "input"))
    )
    (net (code "110") (name "unconnected-(U2-USBPE3-Pad21)") (class "Default")
      (node (ref "U2") (pin "21") (pinfunction "USBPE3_21") (pintype "input"))
    )
    (net (code "111") (name "unconnected-(U2-USBPE4-Pad39)") (class "Default")
      (node (ref "U2") (pin "39") (pinfunction "USBPE4_39") (pintype "input"))
    )
    (net (code "112") (name "unconnected-(U2-USBX0-Pad44)") (class "Default")
      (node (ref "U2") (pin "44") (pinfunction "USBX0_44") (pintype "input"))
    )
    (net (code "113") (name "unconnected-(U2-USBXI-Pad45)") (class "Default")
      (node (ref "U2") (pin "45") (pinfunction "USBXI_45") (pintype "input"))
    )
    (net (code "114") (name "unconnected-(U2-VBUSDET0-Pad43)") (class "Default")
      (node (ref "U2") (pin "43") (pinfunction "VBUSDET0_43") (pintype "input"))
    )
    (net (code "115") (name "unconnected-(U2-VCC-Pad11)") (class "Default")
      (node (ref "U2") (pin "11") (pinfunction "VCC_11") (pintype "input"))
    )
    (net (code "116") (name "unconnected-(U2-VCC10-Pad5)") (class "Default")
      (node (ref "U2") (pin "5") (pinfunction "VCC10_5") (pintype "input"))
    )
    (net (code "117") (name "unconnected-(U2-VCC10-Pad8)") (class "Default")
      (node (ref "U2") (pin "8") (pinfunction "VCC10_8") (pintype "input"))
    )
    (net (code "118") (name "unconnected-(U2-VCC10-Pad14)") (class "Default")
      (node (ref "U2") (pin "14") (pinfunction "VCC10_14") (pintype "input"))
    )
    (net (code "119") (name "unconnected-(U2-VCC10-Pad27)") (class "Default")
      (node (ref "U2") (pin "27") (pinfunction "VCC10_27") (pintype "input"))
    )
    (net (code "120") (name "unconnected-(U2-VCC10-Pad33)") (class "Default")
      (node (ref "U2") (pin "33") (pinfunction "VCC10_33") (pintype "input"))
    )
    (net (code "121") (name "unconnected-(U2-VCC10-Pad36)") (class "Default")
      (node (ref "U2") (pin "36") (pinfunction "VCC10_36") (pintype "input"))
    )
    (net (code "122") (name "unconnected-(U2-VCC10-Pad51)") (class "Default")
      (node (ref "U2") (pin "51") (pinfunction "VCC10_51") (pintype "input"))
    )
    (net (code "123") (name "unconnected-(U2-VCC10-Pad54)") (class "Default")
      (node (ref "U2") (pin "54") (pinfunction "VCC10_54") (pintype "input"))
    )
    (net (code "124") (name "unconnected-(U2-VCC33-Pad17)") (class "Default")
      (node (ref "U2") (pin "17") (pinfunction "VCC33_17") (pintype "input"))
    )
    (net (code "125") (name "unconnected-(U2-VCC33-Pad24)") (class "Default")
      (node (ref "U2") (pin "24") (pinfunction "VCC33_24") (pintype "input"))
    )
    (net (code "126") (name "unconnected-(U2-VCC33-Pad46)") (class "Default")
      (node (ref "U2") (pin "46") (pinfunction "VCC33_46") (pintype "input"))
    )
    (net (code "127") (name "unconnected-(U2-VCC33-Pad62)") (class "Default")
      (node (ref "U2") (pin "62") (pinfunction "VCC33_62") (pintype "input"))
    )
    (net (code "128") (name "unconnected-(U2-VCC33-Pad73)") (class "Default")
      (node (ref "U2") (pin "73") (pinfunction "VCC33_73") (pintype "input"))
    )
    (net (code "129") (name "unconnected-(U2-VDD-Pad30)") (class "Default")
      (node (ref "U2") (pin "30") (pinfunction "VDD_30") (pintype "input"))
    )
    (net (code "130") (name "unconnected-(U2-VDD-Pad48)") (class "Default")
      (node (ref "U2") (pin "48") (pinfunction "VDD_48") (pintype "input"))
    )
    (net (code "131") (name "unconnected-(U2-VDD-Pad67)") (class "Default")
      (node (ref "U2") (pin "67") (pinfunction "VDD_67") (pintype "input"))
    )
    (net (code "132") (name "unconnected-(U3-Attached_Status-Pad16)") (class "Default")
      (node (ref "U3") (pin "16") (pinfunction "Attached_Status_16") (pintype "unspecified+no_connect"))
    )
    (net (code "133") (name "unconnected-(U3-CurrentSettingout-Pad14)") (class "Default")
      (node (ref "U3") (pin "14") (pinfunction "CurrentSettingout_14") (pintype "unspecified+no_connect"))
    )
    (net (code "134") (name "unconnected-(U3-CurrentSettingout-Pad15)") (class "Default")
      (node (ref "U3") (pin "15") (pinfunction "CurrentSettingout_15") (pintype "unspecified+no_connect"))
    )
    (net (code "135") (name "unconnected-(U3-High_Z-Pad13)") (class "Default")
      (node (ref "U3") (pin "13") (pinfunction "High_Z_13") (pintype "unspecified"))
    )
    (net (code "136") (name "unconnected-(U3-ORI_STATUS-Pad22)") (class "Default")
      (node (ref "U3") (pin "22") (pinfunction "ORI_STATUS_22") (pintype "unspecified+no_connect"))
    )
    (net (code "137") (name "unconnected-(U3-Vconn_OC-Pad11)") (class "Default")
      (node (ref "U3") (pin "11") (pinfunction "Vconn_OC_11") (pintype "unspecified+no_connect"))
    )
    (net (code "138") (name "unconnected-(U3-Vconn_UVLO-Pad12)") (class "Default")
      (node (ref "U3") (pin "12") (pinfunction "Vconn_UVLO_12") (pintype "unspecified+no_connect"))
    )
    (net (code "139") (name "unconnected-(U4-DM-Pad13)") (class "Default")
      (node (ref "U4") (pin "13") (pinfunction "DM_13") (pintype "input"))
    )
    (net (code "140") (name "unconnected-(U4-DP-Pad15)") (class "Default")
      (node (ref "U4") (pin "15") (pinfunction "DP_15") (pintype "input"))
    )
    (net (code "141") (name "unconnected-(U4-GND-Pad43)") (class "Default")
      (node (ref "U4") (pin "43") (pinfunction "GND_43") (pintype "input"))
    )
    (net (code "142") (name "unconnected-(U4-GPIO0-Pad2)") (class "Default")
      (node (ref "U4") (pin "2") (pinfunction "GPIO0_2") (pintype "input"))
    )
    (net (code "143") (name "unconnected-(U4-GPIO1-Pad3)") (class "Default")
      (node (ref "U4") (pin "3") (pinfunction "GPIO1_3") (pintype "input"))
    )
    (net (code "144") (name "unconnected-(U4-GPIO2-Pad5)") (class "Default")
      (node (ref "U4") (pin "5") (pinfunction "GPIO2_5") (pintype "input"))
    )
    (net (code "145") (name "unconnected-(U4-GPIO3-Pad6)") (class "Default")
      (node (ref "U4") (pin "6") (pinfunction "GPIO3_6") (pintype "input"))
    )
    (net (code "146") (name "unconnected-(U4-GPIO4-Pad8)") (class "Default")
      (node (ref "U4") (pin "8") (pinfunction "GPIO4_8") (pintype "input"))
    )
    (net (code "147") (name "unconnected-(U4-GPIO5-Pad9)") (class "Default")
      (node (ref "U4") (pin "9") (pinfunction "GPIO5_9") (pintype "input"))
    )
    (net (code "148") (name "unconnected-(U4-GPIO6-Pad11)") (class "Default")
      (node (ref "U4") (pin "11") (pinfunction "GPIO6_11") (pintype "input"))
    )
    (net (code "149") (name "unconnected-(U4-GPIO7-Pad41)") (class "Default")
      (node (ref "U4") (pin "41") (pinfunction "GPIO7_41") (pintype "input"))
    )
    (net (code "150") (name "unconnected-(U4-GPIO8-Pad37)") (class "Default")
      (node (ref "U4") (pin "37") (pinfunction "GPIO8_37") (pintype "input"))
    )
    (net (code "151") (name "unconnected-(U4-GPIO9-Pad48)") (class "Default")
      (node (ref "U4") (pin "48") (pinfunction "GPIO9_48") (pintype "input"))
    )
    (net (code "152") (name "unconnected-(U4-LXO-Pad44)") (class "Default")
      (node (ref "U4") (pin "44") (pinfunction "LXO_44") (pintype "input"))
    )
    (net (code "153") (name "unconnected-(U4-MODE0-Pad46)") (class "Default")
      (node (ref "U4") (pin "46") (pinfunction "MODE0_46") (pintype "input"))
    )
    (net (code "154") (name "unconnected-(U4-MODE1-Pad42)") (class "Default")
      (node (ref "U4") (pin "42") (pinfunction "MODE1_42") (pintype "input"))
    )
    (net (code "155") (name "unconnected-(U4-NC-Pad16)") (class "Default")
      (node (ref "U4") (pin "16") (pinfunction "NC_16") (pintype "input"))
    )
    (net (code "156") (name "unconnected-(U4-NC-Pad17)") (class "Default")
      (node (ref "U4") (pin "17") (pinfunction "NC_17") (pintype "input"))
    )
    (net (code "157") (name "unconnected-(U4-NC-Pad25)") (class "Default")
      (node (ref "U4") (pin "25") (pinfunction "NC_25") (pintype "input"))
    )
    (net (code "158") (name "unconnected-(U4-NC-Pad26)") (class "Default")
      (node (ref "U4") (pin "26") (pinfunction "NC_26") (pintype "input"))
    )
    (net (code "159") (name "unconnected-(U4-NC-Pad35)") (class "Default")
      (node (ref "U4") (pin "35") (pinfunction "NC_35") (pintype "input"))
    )
    (net (code "160") (name "unconnected-(U4-NC-Pad47)") (class "Default")
      (node (ref "U4") (pin "47") (pinfunction "NC_47") (pintype "input"))
    )
    (net (code "161") (name "unconnected-(U4-PE-Pad49)") (class "Default")
      (node (ref "U4") (pin "49") (pinfunction "PE_49") (pintype "input"))
    )
    (net (code "162") (name "unconnected-(U4-RST#-Pad38)") (class "Default")
      (node (ref "U4") (pin "38") (pinfunction "RST#_38") (pintype "input"))
    )
    (net (code "163") (name "unconnected-(U4-RXN-Pad31)") (class "Default")
      (node (ref "U4") (pin "31") (pinfunction "RXN_31") (pintype "input"))
    )
    (net (code "164") (name "unconnected-(U4-RXP-Pad30)") (class "Default")
      (node (ref "U4") (pin "30") (pinfunction "RXP_30") (pintype "input"))
    )
    (net (code "165") (name "unconnected-(U4-SSRXN-Pad22)") (class "Default")
      (node (ref "U4") (pin "22") (pinfunction "SSRXN_22") (pintype "input"))
    )
    (net (code "166") (name "unconnected-(U4-SSRXP-Pad23)") (class "Default")
      (node (ref "U4") (pin "23") (pinfunction "SSRXP_23") (pintype "input"))
    )
    (net (code "167") (name "unconnected-(U4-SSTXN-Pad19)") (class "Default")
      (node (ref "U4") (pin "19") (pinfunction "SSTXN_19") (pintype "input"))
    )
    (net (code "168") (name "unconnected-(U4-SSTXP-Pad20)") (class "Default")
      (node (ref "U4") (pin "20") (pinfunction "SSTXP_20") (pintype "input"))
    )
    (net (code "169") (name "unconnected-(U4-TEXT-Pad36)") (class "Default")
      (node (ref "U4") (pin "36") (pinfunction "TEXT_36") (pintype "input"))
    )
    (net (code "170") (name "unconnected-(U4-TME-Pad1)") (class "Default")
      (node (ref "U4") (pin "1") (pinfunction "TME_1") (pintype "input"))
    )
    (net (code "171") (name "unconnected-(U4-TXN-Pad33)") (class "Default")
      (node (ref "U4") (pin "33") (pinfunction "TXN_33") (pintype "input"))
    )
    (net (code "172") (name "unconnected-(U4-TXP-Pad34)") (class "Default")
      (node (ref "U4") (pin "34") (pinfunction "TXP_34") (pintype "input"))
    )
    (net (code "173") (name "unconnected-(U4-VBUS-Pad12)") (class "Default")
      (node (ref "U4") (pin "12") (pinfunction "VBUS_12") (pintype "input"))
    )
    (net (code "174") (name "unconnected-(U4-VCC12-Pad4)") (class "Default")
      (node (ref "U4") (pin "4") (pinfunction "VCC12_4") (pintype "input"))
    )
    (net (code "175") (name "unconnected-(U4-VCC12-Pad10)") (class "Default")
      (node (ref "U4") (pin "10") (pinfunction "VCC12_10") (pintype "input"))
    )
    (net (code "176") (name "unconnected-(U4-VCC12-Pad18)") (class "Default")
      (node (ref "U4") (pin "18") (pinfunction "VCC12_18") (pintype "input"))
    )
    (net (code "177") (name "unconnected-(U4-VCC12-Pad21)") (class "Default")
      (node (ref "U4") (pin "21") (pinfunction "VCC12_21") (pintype "input"))
    )
    (net (code "178") (name "unconnected-(U4-VCC12-Pad24)") (class "Default")
      (node (ref "U4") (pin "24") (pinfunction "VCC12_24") (pintype "input"))
    )
    (net (code "179") (name "unconnected-(U4-VCC12-Pad29)") (class "Default")
      (node (ref "U4") (pin "29") (pinfunction "VCC12_29") (pintype "input"))
    )
    (net (code "180") (name "unconnected-(U4-VCC12-Pad32)") (class "Default")
      (node (ref "U4") (pin "32") (pinfunction "VCC12_32") (pintype "input"))
    )
    (net (code "181") (name "unconnected-(U4-VCC12-Pad40)") (class "Default")
      (node (ref "U4") (pin "40") (pinfunction "VCC12_40") (pintype "input"))
    )
    (net (code "182") (name "unconnected-(U4-VCC33-Pad7)") (class "Default")
      (node (ref "U4") (pin "7") (pinfunction "VCC33_7") (pintype "input"))
    )
    (net (code "183") (name "unconnected-(U4-VCC33-Pad14)") (class "Default")
      (node (ref "U4") (pin "14") (pinfunction "VCC33_14") (pintype "input"))
    )
    (net (code "184") (name "unconnected-(U4-VCC33-Pad39)") (class "Default")
      (node (ref "U4") (pin "39") (pinfunction "VCC33_39") (pintype "input"))
    )
    (net (code "185") (name "unconnected-(U4-VREG_IN-Pad45)") (class "Default")
      (node (ref "U4") (pin "45") (pinfunction "VREG_IN_45") (pintype "input"))
    )
    (net (code "186") (name "unconnected-(U4-XIN-Pad28)") (class "Default")
      (node (ref "U4") (pin "28") (pinfunction "XIN_28") (pintype "input"))
    )
    (net (code "187") (name "unconnected-(U4-XOUT-Pad27)") (class "Default")
      (node (ref "U4") (pin "27") (pinfunction "XOUT_27") (pintype "input"))
    )
    (net (code "188") (name "unconnected-(USB1-SUB1-PadA8)") (class "Default")
      (node (ref "USB1") (pin "A8") (pinfunction "SUB1_A8") (pintype "unspecified+no_connect"))
    )
    (net (code "189") (name "unconnected-(USB1-SUB2-PadB8)") (class "Default")
      (node (ref "USB1") (pin "B8") (pinfunction "SUB2_B8") (pintype "unspecified+no_connect"))
    )
  )
)
